# Sunrise_Alarm_Clock.net
KiCad netlist of a schematic drawn in EAGLE
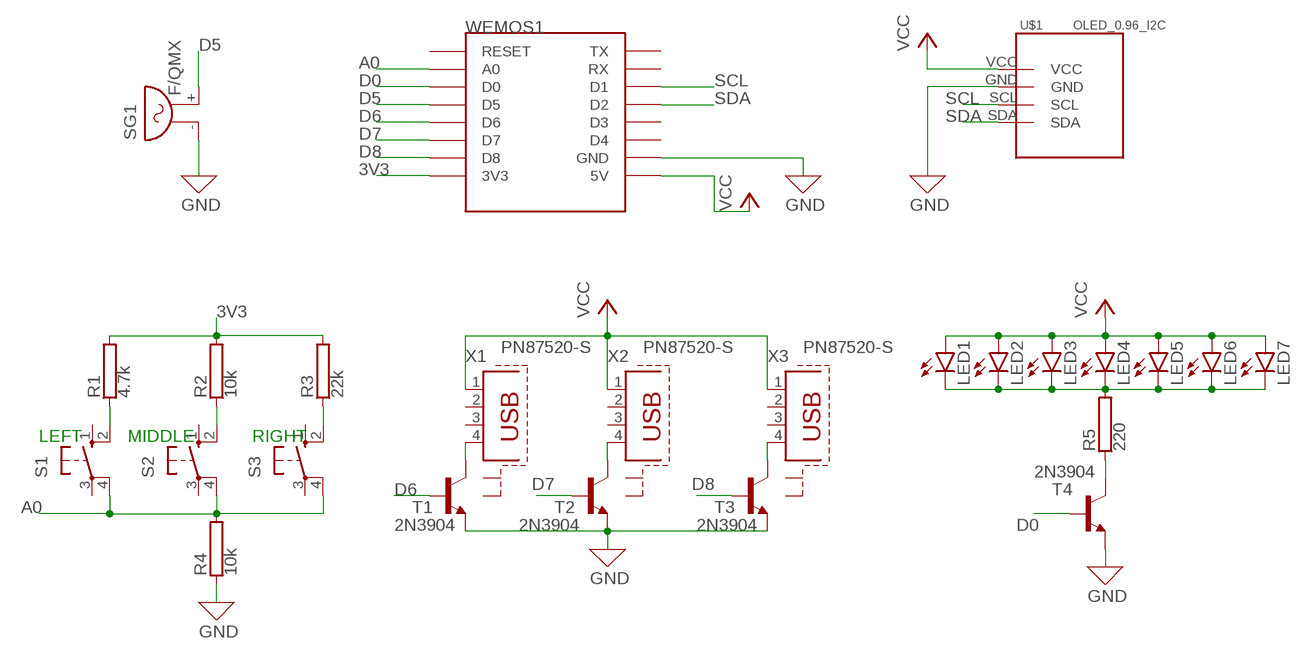
[diagram p0: schematic, sheet 1]

(export (version "E")
  (design (tool "Eeschema 10.0.6"))
  (components
    (comp (ref "LED1")
      (value "LED5MM")
      (footprint "eagle-import:LED5MM")
      (libsource (lib "eagle-import") (part "LED5MM"))
    )
    (comp (ref "LED2")
      (value "LED5MM")
      (footprint "eagle-import:LED5MM")
      (libsource (lib "eagle-import") (part "LED5MM"))
    )
    (comp (ref "LED3")
      (value "LED5MM")
      (footprint "eagle-import:LED5MM")
      (libsource (lib "eagle-import") (part "LED5MM"))
    )
    (comp (ref "LED4")
      (value "LED5MM")
      (footprint "eagle-import:LED5MM")
      (libsource (lib "eagle-import") (part "LED5MM"))
    )
    (comp (ref "LED5")
      (value "LED5MM")
      (footprint "eagle-import:LED5MM")
      (libsource (lib "eagle-import") (part "LED5MM"))
    )
    (comp (ref "LED6")
      (value "LED5MM")
      (footprint "eagle-import:LED5MM")
      (libsource (lib "eagle-import") (part "LED5MM"))
    )
    (comp (ref "LED7")
      (value "LED5MM")
      (footprint "eagle-import:LED5MM")
      (libsource (lib "eagle-import") (part "LED5MM"))
    )
    (comp (ref "R1")
      (value "4.7k")
      (footprint "eagle-import:AC01")
      (libsource (lib "eagle-import") (part "RAC01"))
    )
    (comp (ref "R2")
      (value "10k")
      (footprint "eagle-import:AC01")
      (libsource (lib "eagle-import") (part "RAC01"))
    )
    (comp (ref "R3")
      (value "22k")
      (footprint "eagle-import:AC01")
      (libsource (lib "eagle-import") (part "RAC01"))
    )
    (comp (ref "R4")
      (value "10k")
      (footprint "eagle-import:AC01")
      (libsource (lib "eagle-import") (part "RAC01"))
    )
    (comp (ref "R5")
      (value "220")
      (footprint "eagle-import:AC01")
      (libsource (lib "eagle-import") (part "RAC01"))
    )
    (comp (ref "S1")
      (value "10-XX")
      (footprint "eagle-import:B3F-10XX")
      (fields (field (name "MPN") "B3F-1000"))
      (libsource (lib "eagle-import") (part "10-XX"))
    )
    (comp (ref "S2")
      (value "10-XX")
      (footprint "eagle-import:B3F-10XX")
      (fields (field (name "MPN") "B3F-1000"))
      (libsource (lib "eagle-import") (part "10-XX"))
    )
    (comp (ref "S3")
      (value "10-XX")
      (footprint "eagle-import:B3F-10XX")
      (fields (field (name "MPN") "B3F-1000"))
      (libsource (lib "eagle-import") (part "10-XX"))
    )
    (comp (ref "SG1")
      (value "F/QMX")
      (footprint "eagle-import:F_QMX")
      (libsource (lib "eagle-import") (part "F/QMX"))
    )
    (comp (ref "T1")
      (value "2N3904")
      (footprint "eagle-import:TO92")
      (libsource (lib "eagle-import") (part "2N3904"))
    )
    (comp (ref "T2")
      (value "2N3904")
      (footprint "eagle-import:TO92")
      (libsource (lib "eagle-import") (part "2N3904"))
    )
    (comp (ref "T3")
      (value "2N3904")
      (footprint "eagle-import:TO92")
      (libsource (lib "eagle-import") (part "2N3904"))
    )
    (comp (ref "T4")
      (value "2N3904")
      (footprint "eagle-import:TO92")
      (libsource (lib "eagle-import") (part "2N3904"))
    )
    (comp (ref "U$1")
      (value "OLED_0.96_I2C")
      (footprint "eagle-import:OLED_0.96_I2C")
      (libsource (lib "eagle-import") (part "OLED_0.96_I2C"))
    )
    (comp (ref "WEMOS1")
      (value "WEMOS-D1-MINI")
      (footprint "eagle-import:WEMOS-D1-MINI")
      (libsource (lib "eagle-import") (part "WEMOS-D1-MINI"))
    )
    (comp (ref "X1")
      (value "PN87520-S")
      (footprint "eagle-import:PN87520-S")
      (libsource (lib "eagle-import") (part "PN87520-S"))
    )
    (comp (ref "X2")
      (value "PN87520-S")
      (footprint "eagle-import:PN87520-S")
      (libsource (lib "eagle-import") (part "PN87520-S"))
    )
    (comp (ref "X3")
      (value "PN87520-S")
      (footprint "eagle-import:PN87520-S")
      (libsource (lib "eagle-import") (part "PN87520-S"))
    )
  )
  (nets
    (net (code "1") (name "/3V3") (class "Default")
      (node (ref "R1") (pin "2") (pinfunction "2_2") (pintype "passive"))
      (node (ref "R2") (pin "2") (pinfunction "2_2") (pintype "passive"))
      (node (ref "R3") (pin "2") (pinfunction "2_2") (pintype "passive"))
      (node (ref "WEMOS1") (pin "3V3") (pinfunction "3V3_3V3") (pintype "bidirectional"))
    )
    (net (code "2") (name "/A0") (class "Default")
      (node (ref "R4") (pin "2") (pinfunction "2_2") (pintype "passive"))
      (node (ref "S1") (pin "4") (pinfunction "P1_4") (pintype "passive"))
      (node (ref "S2") (pin "4") (pinfunction "P1_4") (pintype "passive"))
      (node (ref "S3") (pin "4") (pinfunction "P1_4") (pintype "passive"))
      (node (ref "WEMOS1") (pin "A0") (pinfunction "A0_A0") (pintype "bidirectional"))
    )
    (net (code "3") (name "/D0") (class "Default")
      (node (ref "T4") (pin "2") (pinfunction "B_2") (pintype "passive"))
      (node (ref "WEMOS1") (pin "D0") (pinfunction "D0_D0") (pintype "bidirectional"))
    )
    (net (code "4") (name "/D5") (class "Default")
      (node (ref "SG1") (pin "+") (pinfunction "2_+") (pintype "passive"))
      (node (ref "WEMOS1") (pin "D5") (pinfunction "D5_D5") (pintype "bidirectional"))
    )
    (net (code "5") (name "/D6") (class "Default")
      (node (ref "T1") (pin "2") (pinfunction "B_2") (pintype "passive"))
      (node (ref "WEMOS1") (pin "D6") (pinfunction "D6_D6") (pintype "bidirectional"))
    )
    (net (code "6") (name "/D7") (class "Default")
      (node (ref "T2") (pin "2") (pinfunction "B_2") (pintype "passive"))
      (node (ref "WEMOS1") (pin "D7") (pinfunction "D7_D7") (pintype "bidirectional"))
    )
    (net (code "7") (name "/D8") (class "Default")
      (node (ref "T3") (pin "2") (pinfunction "B_2") (pintype "passive"))
      (node (ref "WEMOS1") (pin "D8") (pinfunction "D8_D8") (pintype "bidirectional"))
    )
    (net (code "8") (name "/SCL") (class "Default")
      (node (ref "U$1") (pin "SCL") (pinfunction "SCL_SCL") (pintype "bidirectional"))
      (node (ref "WEMOS1") (pin "D1") (pinfunction "D1_D1") (pintype "bidirectional"))
    )
    (net (code "9") (name "/SDA") (class "Default")
      (node (ref "U$1") (pin "SDA") (pinfunction "SDA_SDA") (pintype "bidirectional"))
      (node (ref "WEMOS1") (pin "D2") (pinfunction "D2_D2") (pintype "bidirectional"))
    )
    (net (code "10") (name "GND") (class "Default")
      (node (ref "R4") (pin "1") (pinfunction "1_1") (pintype "passive"))
      (node (ref "SG1") (pin "-") (pinfunction "1_-") (pintype "passive"))
      (node (ref "T1") (pin "3") (pinfunction "E_3") (pintype "passive"))
      (node (ref "T2") (pin "3") (pinfunction "E_3") (pintype "passive"))
      (node (ref "T3") (pin "3") (pinfunction "E_3") (pintype "passive"))
      (node (ref "T4") (pin "3") (pinfunction "E_3") (pintype "passive"))
      (node (ref "U$1") (pin "GND") (pinfunction "GND_GND") (pintype "bidirectional"))
      (node (ref "WEMOS1") (pin "GND") (pinfunction "GND_GND") (pintype "bidirectional"))
    )
    (net (code "11") (name "Net-(LED1-C)") (class "Default")
      (node (ref "LED1") (pin "K") (pinfunction "C_K") (pintype "passive"))
      (node (ref "LED2") (pin "K") (pinfunction "C_K") (pintype "passive"))
      (node (ref "LED3") (pin "K") (pinfunction "C_K") (pintype "passive"))
      (node (ref "LED4") (pin "K") (pinfunction "C_K") (pintype "passive"))
      (node (ref "LED5") (pin "K") (pinfunction "C_K") (pintype "passive"))
      (node (ref "LED6") (pin "K") (pinfunction "C_K") (pintype "passive"))
      (node (ref "LED7") (pin "K") (pinfunction "C_K") (pintype "passive"))
      (node (ref "R5") (pin "2") (pinfunction "2_2") (pintype "passive"))
    )
    (net (code "12") (name "Net-(S1-S1)") (class "Default")
      (node (ref "R1") (pin "1") (pinfunction "1_1") (pintype "passive"))
      (node (ref "S1") (pin "2") (pinfunction "S1_2") (pintype "passive"))
    )
    (net (code "13") (name "Net-(S2-S1)") (class "Default")
      (node (ref "R2") (pin "1") (pinfunction "1_1") (pintype "passive"))
      (node (ref "S2") (pin "2") (pinfunction "S1_2") (pintype "passive"))
    )
    (net (code "14") (name "Net-(S3-S1)") (class "Default")
      (node (ref "R3") (pin "1") (pinfunction "1_1") (pintype "passive"))
      (node (ref "S3") (pin "2") (pinfunction "S1_2") (pintype "passive"))
    )
    (net (code "15") (name "Net-(T1-C)") (class "Default")
      (node (ref "T1") (pin "1") (pinfunction "C_1") (pintype "passive"))
      (node (ref "X1") (pin "4") (pinfunction "4_4") (pintype "passive"))
    )
    (net (code "16") (name "Net-(T2-C)") (class "Default")
      (node (ref "T2") (pin "1") (pinfunction "C_1") (pintype "passive"))
      (node (ref "X2") (pin "4") (pinfunction "4_4") (pintype "passive"))
    )
    (net (code "17") (name "Net-(T3-C)") (class "Default")
      (node (ref "T3") (pin "1") (pinfunction "C_1") (pintype "passive"))
      (node (ref "X3") (pin "4") (pinfunction "4_4") (pintype "passive"))
    )
    (net (code "18") (name "Net-(T4-C)") (class "Default")
      (node (ref "R5") (pin "1") (pinfunction "1_1") (pintype "passive"))
      (node (ref "T4") (pin "1") (pinfunction "C_1") (pintype "passive"))
    )
    (net (code "19") (name "VCC") (class "Default")
      (node (ref "LED1") (pin "A") (pinfunction "A_A") (pintype "passive"))
      (node (ref "LED2") (pin "A") (pinfunction "A_A") (pintype "passive"))
      (node (ref "LED3") (pin "A") (pinfunction "A_A") (pintype "passive"))
      (node (ref "LED4") (pin "A") (pinfunction "A_A") (pintype "passive"))
      (node (ref "LED5") (pin "A") (pinfunction "A_A") (pintype "passive"))
      (node (ref "LED6") (pin "A") (pinfunction "A_A") (pintype "passive"))
      (node (ref "LED7") (pin "A") (pinfunction "A_A") (pintype "passive"))
      (node (ref "U$1") (pin "VCC") (pinfunction "VCC_VCC") (pintype "bidirectional"))
      (node (ref "WEMOS1") (pin "5V") (pinfunction "5V_5V") (pintype "bidirectional"))
      (node (ref "X1") (pin "1") (pinfunction "1_1") (pintype "passive"))
      (node (ref "X2") (pin "1") (pinfunction "1_1") (pintype "passive"))
      (node (ref "X3") (pin "1") (pinfunction "1_1") (pintype "passive"))
    )
    (net (code "20") (name "unconnected-(S1-P-Pad3)") (class "Default")
      (node (ref "S1") (pin "3") (pinfunction "P_3") (pintype "passive"))
    )
    (net (code "21") (name "unconnected-(S1-S-Pad1)") (class "Default")
      (node (ref "S1") (pin "1") (pinfunction "S_1") (pintype "passive"))
    )
    (net (code "22") (name "unconnected-(S2-P-Pad3)") (class "Default")
      (node (ref "S2") (pin "3") (pinfunction "P_3") (pintype "passive"))
    )
    (net (code "23") (name "unconnected-(S2-S-Pad1)") (class "Default")
      (node (ref "S2") (pin "1") (pinfunction "S_1") (pintype "passive"))
    )
    (net (code "24") (name "unconnected-(S3-P-Pad3)") (class "Default")
      (node (ref "S3") (pin "3") (pinfunction "P_3") (pintype "passive"))
    )
    (net (code "25") (name "unconnected-(S3-S-Pad1)") (class "Default")
      (node (ref "S3") (pin "1") (pinfunction "S_1") (pintype "passive"))
    )
    (net (code "26") (name "unconnected-(WEMOS1-PadD3)") (class "Default")
      (node (ref "WEMOS1") (pin "D3") (pinfunction "D3_D3") (pintype "bidirectional"))
    )
    (net (code "27") (name "unconnected-(WEMOS1-PadD4)") (class "Default")
      (node (ref "WEMOS1") (pin "D4") (pinfunction "D4_D4") (pintype "bidirectional"))
    )
    (net (code "28") (name "unconnected-(WEMOS1-PadRESET)") (class "Default")
      (node (ref "WEMOS1") (pin "RESET") (pinfunction "RESET_RESET") (pintype "bidirectional"))
    )
    (net (code "29") (name "unconnected-(WEMOS1-PadRX)") (class "Default")
      (node (ref "WEMOS1") (pin "RX") (pinfunction "RX_RX") (pintype "bidirectional"))
    )
    (net (code "30") (name "unconnected-(WEMOS1-PadTX)") (class "Default")
      (node (ref "WEMOS1") (pin "TX") (pinfunction "TX_TX") (pintype "bidirectional"))
    )
    (net (code "31") (name "unconnected-(X1-Pad2)") (class "Default")
      (node (ref "X1") (pin "2") (pinfunction "2_2") (pintype "passive"))
    )
    (net (code "32") (name "unconnected-(X1-Pad3)") (class "Default")
      (node (ref "X1") (pin "3") (pinfunction "3_3") (pintype "passive"))
    )
    (net (code "33") (name "unconnected-(X1-PadS1)") (class "Default")
      (node (ref "X1") (pin "S1") (pinfunction "S1_S1") (pintype "passive"))
    )
    (net (code "34") (name "unconnected-(X1-PadS2)") (class "Default")
      (node (ref "X1") (pin "S2") (pinfunction "S2_S2") (pintype "passive"))
    )
    (net (code "35") (name "unconnected-(X2-Pad2)") (class "Default")
      (node (ref "X2") (pin "2") (pinfunction "2_2") (pintype "passive"))
    )
    (net (code "36") (name "unconnected-(X2-Pad3)") (class "Default")
      (node (ref "X2") (pin "3") (pinfunction "3_3") (pintype "passive"))
    )
    (net (code "37") (name "unconnected-(X2-PadS1)") (class "Default")
      (node (ref "X2") (pin "S1") (pinfunction "S1_S1") (pintype "passive"))
    )
    (net (code "38") (name "unconnected-(X2-PadS2)") (class "Default")
      (node (ref "X2") (pin "S2") (pinfunction "S2_S2") (pintype "passive"))
    )
    (net (code "39") (name "unconnected-(X3-Pad2)") (class "Default")
      (node (ref "X3") (pin "2") (pinfunction "2_2") (pintype "passive"))
    )
    (net (code "40") (name "unconnected-(X3-Pad3)") (class "Default")
      (node (ref "X3") (pin "3") (pinfunction "3_3") (pintype "passive"))
    )
    (net (code "41") (name "unconnected-(X3-PadS1)") (class "Default")
      (node (ref "X3") (pin "S1") (pinfunction "S1_S1") (pintype "passive"))
    )
    (net (code "42") (name "unconnected-(X3-PadS2)") (class "Default")
      (node (ref "X3") (pin "S2") (pinfunction "S2_S2") (pintype "passive"))
    )
  )
)
